# Teensylu2-0_8.net
KiCad netlist of a schematic drawn in EAGLE
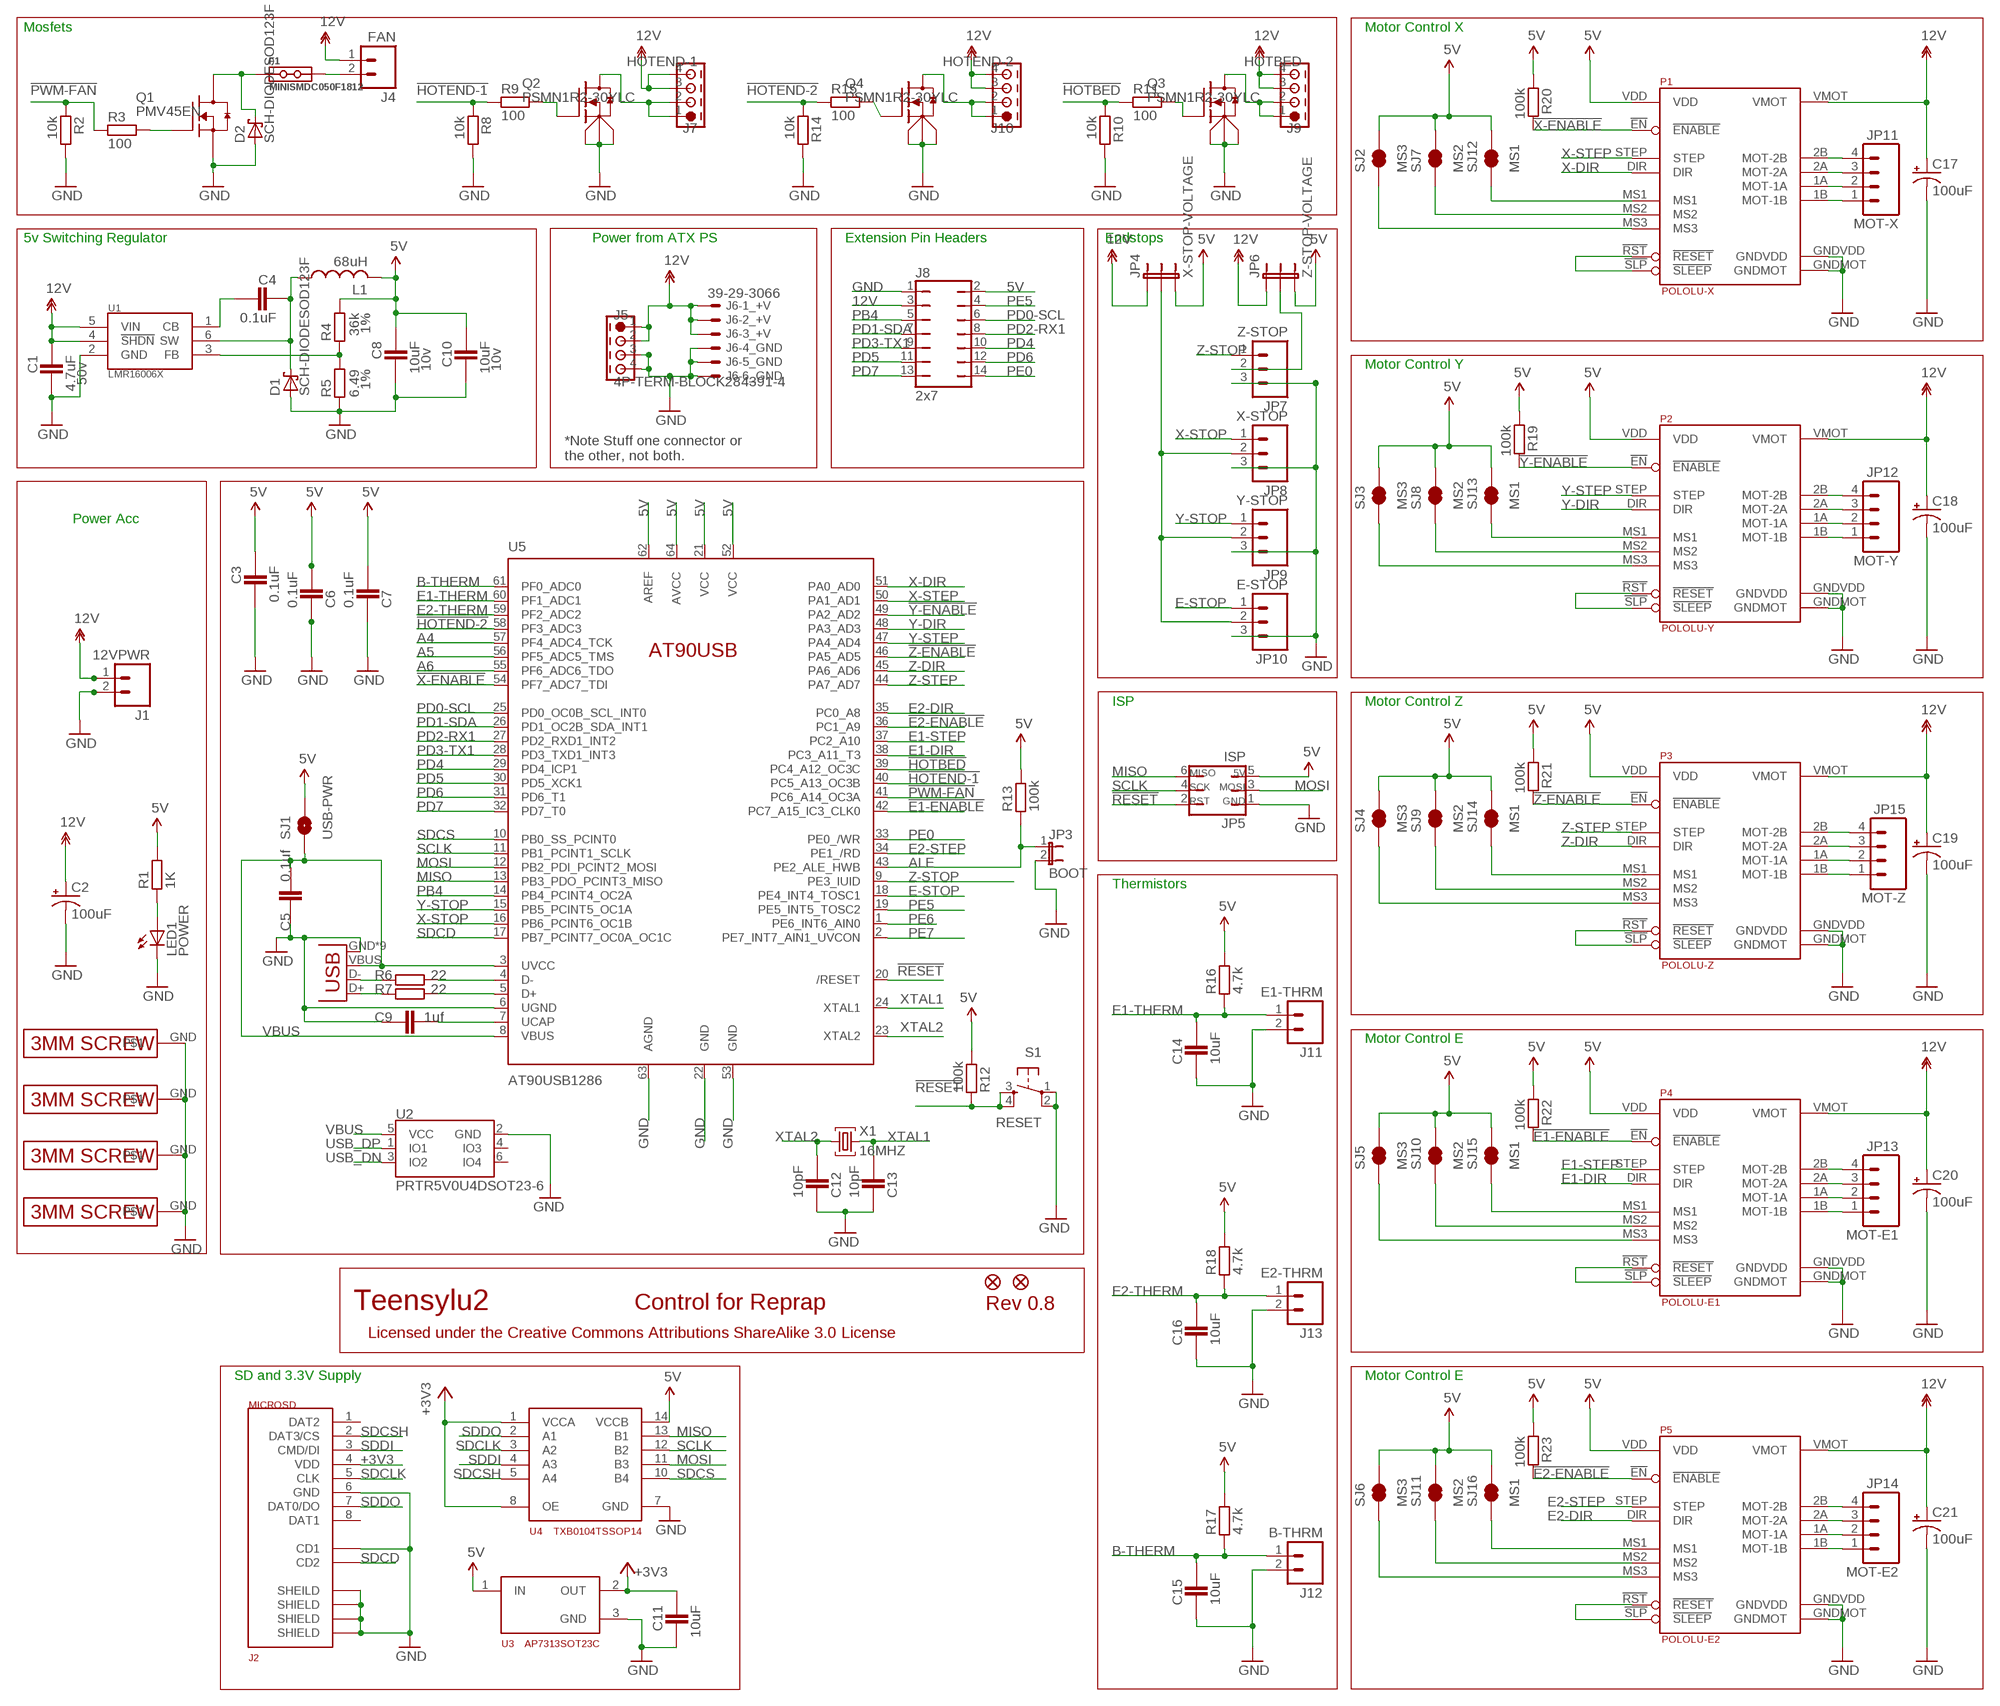
[diagram p0: schematic, sheet 1]

(export (version "E")
  (design (tool "Eeschema 10.0.6"))
  (components
    (comp (ref "C1")
      (value "4.7uF")
      (footprint "eagle-import:CAPC3215X168N")
      (fields
        (field (name "MANUFACTURER") "Yaiyo Yuden")
        (field (name "MANUFACTURER_PART_NUMBER") "UMK316AB7475KL-T")
        (field (name "VDC") "50v")
      )
      (libsource (lib "eagle-import") (part "CAPACITOR_1206"))
    )
    (comp (ref "C2")
      (value "100uF")
      (footprint "eagle-import:PANASONIC_D")
      (fields
        (field (name "MANUFACTURER") "Panasonic")
        (field (name "MANUFACTURER_PART_NUMBER") "EEE-FTH101XAP")
        (field (name "TOLERANCE") "20%")
      )
      (libsource (lib "eagle-import") (part "CPOL-USD"))
    )
    (comp (ref "C3")
      (value "0.1uF")
      (footprint "eagle-import:CAPC1608X92N")
      (fields
        (field (name "MANUFACTURER") "Murata")
        (field (name "MANUFACTURER_PART_NUMBER") "GRM188R71C104KA01D")
        (field (name "TOLERANCE") "10%")
      )
      (libsource (lib "eagle-import") (part "CAPACITOR_0603"))
    )
    (comp (ref "C4")
      (value "0.1uF")
      (footprint "eagle-import:CAPC1608X92N")
      (fields
        (field (name "MANUFACTURER") "Samsung")
        (field (name "MANUFACTURER_PART_NUMBER") "CL10B104KB8NNNC")
        (field (name "TOLERANCE") "10%")
      )
      (libsource (lib "eagle-import") (part "CAPACITOR_0603"))
    )
    (comp (ref "C5")
      (value "0.1uf")
      (footprint "eagle-import:CAPC1608X92N")
      (libsource (lib "eagle-import") (part "CAPACITOR_0603"))
    )
    (comp (ref "C6")
      (value "0.1uF")
      (footprint "eagle-import:CAPC1608X92N")
      (fields
        (field (name "MANUFACTURER") "Murata")
        (field (name "MANUFACTURER_PART_NUMBER") "GRM188R71C104KA01D")
        (field (name "TOLERANCE") "10%")
      )
      (libsource (lib "eagle-import") (part "CAPACITOR_0603"))
    )
    (comp (ref "C7")
      (value "0.1uF")
      (footprint "eagle-import:CAPC1608X92N")
      (fields
        (field (name "MANUFACTURER") "Murata")
        (field (name "MANUFACTURER_PART_NUMBER") "GRM188R71C104KA01D")
        (field (name "TOLERANCE") "10%")
      )
      (libsource (lib "eagle-import") (part "CAPACITOR_0603"))
    )
    (comp (ref "C8")
      (value "10uF")
      (footprint "eagle-import:CAPC2012X145AN")
      (fields
        (field (name "MANUFACTURER") "Murata")
        (field (name "MANUFACTURER_PART_NUMBER") "GRM21BR71A106KE51L")
        (field (name "TOLERANCE") "10%")
        (field (name "VDC") "10v")
      )
      (libsource (lib "eagle-import") (part "CAPACITOR_0805"))
    )
    (comp (ref "C9")
      (value "1uf")
      (footprint "eagle-import:CAPC1608X92N")
      (fields
        (field (name "MANUFACTURER") "Samsung")
        (field (name "MANUFACTURER_PART_NUMBER") "CL10A105MO8NNNC")
        (field (name "TOLERANCE") "20%")
      )
      (libsource (lib "eagle-import") (part "CAPACITOR_0603"))
    )
    (comp (ref "C10")
      (value "10uF")
      (footprint "eagle-import:CAPC2012X145AN")
      (fields
        (field (name "MANUFACTURER") "Murata")
        (field (name "MANUFACTURER_PART_NUMBER") "GRM21BR71A106KE51L")
        (field (name "TOLERANCE") "10%")
        (field (name "VDC") "10v")
      )
      (libsource (lib "eagle-import") (part "CAPACITOR_0805"))
    )
    (comp (ref "C11")
      (value "10uF")
      (footprint "eagle-import:CAPC1608X92N")
      (fields
        (field (name "MANUFACTURER") "Murata")
        (field (name "MANUFACTURER_PART_NUMBER") "GRM188R61C106MA73D")
        (field (name "TOLERANCE") "20%")
      )
      (libsource (lib "eagle-import") (part "CAPACITOR_0603"))
    )
    (comp (ref "C12")
      (value "10pF")
      (footprint "eagle-import:CAPC1608X92N")
      (fields
        (field (name "MANUFACTURER") "Samsung")
        (field (name "MANUFACTURER_PART_NUMBER") "CL10C100JB8NCNC")
        (field (name "TOLERANCE") "5%")
      )
      (libsource (lib "eagle-import") (part "CAPACITOR_0603"))
    )
    (comp (ref "C13")
      (value "10pF")
      (footprint "eagle-import:CAPC1608X92N")
      (fields
        (field (name "MANUFACTURER") "Samsung")
        (field (name "MANUFACTURER_PART_NUMBER") "CL10C100JB8NCNC")
        (field (name "TOLERANCE") "5%")
      )
      (libsource (lib "eagle-import") (part "CAPACITOR_0603"))
    )
    (comp (ref "C14")
      (value "10uF")
      (footprint "eagle-import:CAPC1608X92N")
      (fields
        (field (name "MANUFACTURER") "Murata")
        (field (name "MANUFACTURER_PART_NUMBER") "GRM188R61C106MA73D")
        (field (name "TOLERANCE") "20%")
      )
      (libsource (lib "eagle-import") (part "CAPACITOR_0603"))
    )
    (comp (ref "C15")
      (value "10uF")
      (footprint "eagle-import:CAPC1608X92N")
      (fields
        (field (name "MANUFACTURER") "Murata")
        (field (name "MANUFACTURER_PART_NUMBER") "GRM188R61C106MA73D")
        (field (name "TOLERANCE") "20%")
      )
      (libsource (lib "eagle-import") (part "CAPACITOR_0603"))
    )
    (comp (ref "C16")
      (value "10uF")
      (footprint "eagle-import:CAPC1608X92N")
      (fields
        (field (name "MANUFACTURER") "Murata")
        (field (name "MANUFACTURER_PART_NUMBER") "GRM188R61C106MA73D")
        (field (name "TOLERANCE") "20%")
      )
      (libsource (lib "eagle-import") (part "CAPACITOR_0603"))
    )
    (comp (ref "C17")
      (value "100uF")
      (footprint "eagle-import:PANASONIC_D")
      (fields
        (field (name "MANUFACTURER") "Panasonic")
        (field (name "MANUFACTURER_PART_NUMBER") "EEE-FTH101XAP")
        (field (name "TOLERANCE") "20%")
      )
      (libsource (lib "eagle-import") (part "CPOL-USD"))
    )
    (comp (ref "C18")
      (value "100uF")
      (footprint "eagle-import:PANASONIC_D")
      (fields
        (field (name "MANUFACTURER") "Panasonic")
        (field (name "MANUFACTURER_PART_NUMBER") "EEE-FTH101XAP")
        (field (name "TOLERANCE") "20%")
      )
      (libsource (lib "eagle-import") (part "CPOL-USD"))
    )
    (comp (ref "C19")
      (value "100uF")
      (footprint "eagle-import:PANASONIC_D")
      (fields
        (field (name "MANUFACTURER") "Panasonic")
        (field (name "MANUFACTURER_PART_NUMBER") "EEE-FTH101XAP")
        (field (name "TOLERANCE") "20%")
      )
      (libsource (lib "eagle-import") (part "CPOL-USD"))
    )
    (comp (ref "C20")
      (value "100uF")
      (footprint "eagle-import:PANASONIC_D")
      (fields
        (field (name "MANUFACTURER") "Panasonic")
        (field (name "MANUFACTURER_PART_NUMBER") "EEE-FTH101XAP")
        (field (name "TOLERANCE") "20%")
      )
      (libsource (lib "eagle-import") (part "CPOL-USD"))
    )
    (comp (ref "C21")
      (value "100uF")
      (footprint "eagle-import:PANASONIC_D")
      (fields
        (field (name "MANUFACTURER") "Panasonic")
        (field (name "MANUFACTURER_PART_NUMBER") "EEE-FTH101XAP")
        (field (name "TOLERANCE") "20%")
      )
      (libsource (lib "eagle-import") (part "CPOL-USD"))
    )
    (comp (ref "D1")
      (value "SCH-DIODESOD123F")
      (footprint "eagle-import:SOD123F")
      (fields
        (field (name "MANUFACTURER") "NXP Semiconductors")
        (field (name "MANUFACTURER_PART_NUMBER") "PMEG4010CEH,115")
        (field (name "CURRENT") "1A")
        (field (name "MANUFACTURER_1") "NXP Semiconductors")
        (field (name "MANUFACTURER_PART_NUMBER_1") "PMEG4010CEH,115")
        (field (name "REVERSE_VOLTAGE") "40V")
      )
      (libsource (lib "eagle-import") (part "SCH-DIODESOD123F"))
    )
    (comp (ref "D2")
      (value "SCH-DIODESOD123F")
      (footprint "eagle-import:SOD123F")
      (fields
        (field (name "MANUFACTURER") "NXP Semiconductors")
        (field (name "MANUFACTURER_PART_NUMBER") "PMEG4010CEH,115")
        (field (name "CURRENT") "1A")
        (field (name "MANUFACTURER_1") "NXP Semiconductors")
      )
      (libsource (lib "eagle-import") (part "SCH-DIODESOD123F"))
    )
    (comp (ref "F1")
      (value "MINISMDC050F1812")
      (footprint "eagle-import:MINISMDC")
      (fields
        (field (name "MANUFACTURER") "TE Connectivity")
        (field (name "MANUFACTURER_PART_NUMBER") "MINISMDC050F-2")
      )
      (libsource (lib "eagle-import") (part "MINISMDC050F1812"))
    )
    (comp (ref "J1")
      (value "12VPWR")
      (footprint "eagle-import:MOLEX-1X2")
      (libsource (lib "eagle-import") (part "M02POLAR"))
    )
    (comp (ref "J2")
      (value "MICROSD")
      (footprint "eagle-import:AMPHENOL-MICROSD")
      (fields
        (field (name "MANUFACTURER") "Amphenol")
        (field (name "MANUFACTURER_PART_NUMBER") "114-00841-68")
      )
      (libsource (lib "eagle-import") (part "MICROSD"))
    )
    (comp (ref "J3")
      (value "USB-MICRO-PTH")
      (footprint "eagle-import:USB-MICROB-PTH")
      (fields (field (name "MANUFACTURER") "FCI") (field (name "MANUFACTURER_PART_NUMBER") "10118194-0001LF"))
      (libsource (lib "eagle-import") (part "USB-MICRO-PTH"))
    )
    (comp (ref "J4")
      (value "FAN")
      (footprint "eagle-import:MOLEX-1X2")
      (libsource (lib "eagle-import") (part "M02POLAR"))
    )
    (comp (ref "J5")
      (value "4P-TERM-BLOCK284391-4")
      (footprint "eagle-import:284391-4")
      (fields
        (field (name "MANUFACTURER") "TE Connectivity")
        (field (name "MANUFACTURER_PART_NUMBER") "284391-4")
      )
      (libsource (lib "eagle-import") (part "4P-TERM-BLOCK284391-4"))
    )
    (comp (ref "J6")
      (value "39-29-3066")
      (footprint "eagle-import:39-29-3066")
      (fields (field (name "MANUFACTURER") "Molex") (field (name "MANUFACTURER_PART_NUMBER") "0039293066"))
      (libsource (lib "eagle-import") (part "39-29-3066"))
    )
    (comp (ref "J7")
      (value "HOTEND-1")
      (footprint "eagle-import:282834-4")
      (fields
        (field (name "MANUFACTURER") "TE Connectivity")
        (field (name "MANUFACTURER_PART_NUMBER") "282834-4")
      )
      (libsource (lib "eagle-import") (part "4P-TERM-BLOCK282834-4"))
    )
    (comp (ref "J8")
      (value "2x7")
      (footprint "eagle-import:JP7Q")
      (libsource (lib "eagle-import") (part "JP7Q"))
    )
    (comp (ref "J9")
      (value "HOTBED")
      (footprint "eagle-import:284391-4")
      (fields
        (field (name "MANUFACTURER") "TE Connectivity")
        (field (name "MANUFACTURER_PART_NUMBER") "284391-4")
      )
      (libsource (lib "eagle-import") (part "4P-TERM-BLOCK284391-4"))
    )
    (comp (ref "J10")
      (value "HOTEND-2")
      (footprint "eagle-import:282834-4")
      (fields
        (field (name "MANUFACTURER") "TE Connectivity")
        (field (name "MANUFACTURER_PART_NUMBER") "282834-4")
      )
      (libsource (lib "eagle-import") (part "4P-TERM-BLOCK282834-4"))
    )
    (comp (ref "J11")
      (value "E1-THRM")
      (footprint "eagle-import:MOLEX-1X2")
      (libsource (lib "eagle-import") (part "M02POLAR"))
    )
    (comp (ref "J12")
      (value "B-THRM")
      (footprint "eagle-import:MOLEX-1X2")
      (libsource (lib "eagle-import") (part "M02POLAR"))
    )
    (comp (ref "J13")
      (value "E2-THRM")
      (footprint "eagle-import:MOLEX-1X2")
      (libsource (lib "eagle-import") (part "M02POLAR"))
    )
    (comp (ref "JP1")
      (value "FIDUCIAL1X2.5")
      (footprint "eagle-import:FIDUCIAL-1X2.5")
      (libsource (lib "eagle-import") (part "FIDUCIAL1X2.5"))
    )
    (comp (ref "JP2")
      (value "FIDUCIAL1X2.5")
      (footprint "eagle-import:FIDUCIAL-1X2.5")
      (libsource (lib "eagle-import") (part "FIDUCIAL1X2.5"))
    )
    (comp (ref "JP3")
      (value "BOOT")
      (footprint "eagle-import:1X02")
      (libsource (lib "eagle-import") (part "JUMPER-2PTH"))
    )
    (comp (ref "JP4")
      (value "X-STOP-VOLTAGE")
      (footprint "eagle-import:1X03")
      (libsource (lib "eagle-import") (part "JUMPER-3PTH"))
    )
    (comp (ref "JP5")
      (value "ISP")
      (footprint "eagle-import:ISP")
      (libsource (lib "eagle-import") (part "PROGHEADER"))
    )
    (comp (ref "JP6")
      (value "Z-STOP-VOLTAGE")
      (footprint "eagle-import:1X03")
      (libsource (lib "eagle-import") (part "JUMPER-3PTH"))
    )
    (comp (ref "JP7")
      (value "Z-STOP")
      (footprint "eagle-import:MOLEX-1X3")
      (libsource (lib "eagle-import") (part "M03POLAR"))
    )
    (comp (ref "JP8")
      (value "X-STOP")
      (footprint "eagle-import:MOLEX-1X3")
      (libsource (lib "eagle-import") (part "M03POLAR"))
    )
    (comp (ref "JP9")
      (value "Y-STOP")
      (footprint "eagle-import:MOLEX-1X3")
      (libsource (lib "eagle-import") (part "M03POLAR"))
    )
    (comp (ref "JP10")
      (value "E-STOP")
      (footprint "eagle-import:MOLEX-1X3")
      (libsource (lib "eagle-import") (part "M03POLAR"))
    )
    (comp (ref "JP11")
      (value "MOT-X")
      (footprint "eagle-import:MOLEX-1X4")
      (libsource (lib "eagle-import") (part "M04POLAR"))
    )
    (comp (ref "JP12")
      (value "MOT-Y")
      (footprint "eagle-import:MOLEX-1X4")
      (libsource (lib "eagle-import") (part "M04POLAR"))
    )
    (comp (ref "JP13")
      (value "MOT-E1")
      (footprint "eagle-import:MOLEX-1X4")
      (libsource (lib "eagle-import") (part "M04POLAR"))
    )
    (comp (ref "JP14")
      (value "MOT-E2")
      (footprint "eagle-import:MOLEX-1X4")
      (libsource (lib "eagle-import") (part "M04POLAR"))
    )
    (comp (ref "JP15")
      (value "MOT-Z")
      (footprint "eagle-import:MOLEX-1X4")
      (libsource (lib "eagle-import") (part "M04POLAR"))
    )
    (comp (ref "L1")
      (value "68uH")
      (footprint "eagle-import:SRN6045")
      (fields
        (field (name "MANUFACTURER") "Bourns")
        (field (name "MANUFACTURER_PART_NUMBER") "SRN6045-680M")
        (field (name "MANUFACTURER_1") "Bourns")
        (field (name "MANUFACTURER_PART_NUMBER_1") "SRN6045-680M")
      )
      (libsource (lib "eagle-import") (part "INDUCTORSRN6045"))
    )
    (comp (ref "LED1")
      (value "POWER")
      (footprint "eagle-import:CHIPLED_0805")
      (fields
        (field (name "MANUFACTURER") "Kingbright")
        (field (name "MANUFACTURER_PART_NUMBER") "APT2012SGC")
      )
      (libsource (lib "eagle-import") (part "LEDCHIPLED_0805"))
    )
    (comp (ref "P1")
      (value "POLOLU-X")
      (footprint "eagle-import:POLOLU-STEPPER-PTH")
      (libsource (lib "eagle-import") (part "POLOLU-ALLEGRO"))
    )
    (comp (ref "P2")
      (value "POLOLU-Y")
      (footprint "eagle-import:POLOLU-STEPPER-PTH")
      (libsource (lib "eagle-import") (part "POLOLU-ALLEGRO"))
    )
    (comp (ref "P3")
      (value "POLOLU-Z")
      (footprint "eagle-import:POLOLU-STEPPER-PTH")
      (libsource (lib "eagle-import") (part "POLOLU-ALLEGRO"))
    )
    (comp (ref "P4")
      (value "POLOLU-E1")
      (footprint "eagle-import:POLOLU-STEPPER-PTH")
      (libsource (lib "eagle-import") (part "POLOLU-ALLEGRO"))
    )
    (comp (ref "P5")
      (value "POLOLU-E2")
      (footprint "eagle-import:POLOLU-STEPPER-PTH")
      (libsource (lib "eagle-import") (part "POLOLU-ALLEGRO"))
    )
    (comp (ref "Q1")
      (value "PMV45EN")
      (footprint "eagle-import:SOT23C")
      (fields
        (field (name "MANUFACTURER") "International Rectifier")
        (field (name "MANUFACTURER_PART_NUMBER") "IRLML2060TRPBF")
        (field (name "VOLTAGE") "60V")
      )
      (libsource (lib "eagle-import") (part "MOSFET-NCH_SOT-23"))
    )
    (comp (ref "Q2")
      (value "PSMN1R2-30YLC")
      (footprint "eagle-import:LFPACK-POWERPAK-SO8")
      (fields
        (field (name "MANUFACTURER") "NXP Semiconductors")
        (field (name "MANUFACTURER_PART_NUMBER") "PSMN1R2-30YLC,115")
        (field (name "VOLTAGE") "30V")
      )
      (libsource (lib "eagle-import") (part "PSMN1R2-30YLCPOWERPACK-S08"))
    )
    (comp (ref "Q3")
      (value "PSMN1R2-30YLC")
      (footprint "eagle-import:LFPACK-POWERPAK-SO8")
      (fields
        (field (name "MANUFACTURER") "NXP Semiconductors")
        (field (name "MANUFACTURER_PART_NUMBER") "PSMN1R2-30YLC,115")
        (field (name "VOLTAGE") "30V")
      )
      (libsource (lib "eagle-import") (part "PSMN1R2-30YLCPOWERPACK-S08"))
    )
    (comp (ref "Q4")
      (value "PSMN1R2-30YLC")
      (footprint "eagle-import:LFPACK-POWERPAK-SO8")
      (fields
        (field (name "MANUFACTURER") "NXP Semiconductors")
        (field (name "MANUFACTURER_PART_NUMBER") "PSMN1R2-30YLC,115")
        (field (name "VOLTAGE") "30V")
      )
      (libsource (lib "eagle-import") (part "PSMN1R2-30YLCPOWERPACK-S08"))
    )
    (comp (ref "R1")
      (value "1K")
      (footprint "eagle-import:RESC1608X55N")
      (libsource (lib "eagle-import") (part "RESISTOR_0603"))
    )
    (comp (ref "R2")
      (value "10k")
      (footprint "eagle-import:RESC1608X55N")
      (libsource (lib "eagle-import") (part "RESISTOR_0603"))
    )
    (comp (ref "R3")
      (value "100")
      (footprint "eagle-import:RESC1608X55N")
      (libsource (lib "eagle-import") (part "RESISTOR_0603"))
    )
    (comp (ref "R4")
      (value "36k")
      (footprint "eagle-import:RESC1608X55N")
      (fields (field (name "TOLERANCE") "1%"))
      (libsource (lib "eagle-import") (part "RESISTOR_0603"))
    )
    (comp (ref "R5")
      (value "6.49")
      (footprint "eagle-import:RESC1608X55N")
      (fields (field (name "TOLERANCE") "1%"))
      (libsource (lib "eagle-import") (part "RESISTOR_0603"))
    )
    (comp (ref "R6")
      (value "22")
      (footprint "eagle-import:RESC1608X55N")
      (libsource (lib "eagle-import") (part "RESISTOR_0603"))
    )
    (comp (ref "R7")
      (value "22")
      (footprint "eagle-import:RESC1608X55N")
      (libsource (lib "eagle-import") (part "RESISTOR_0603"))
    )
    (comp (ref "R8")
      (value "10k")
      (footprint "eagle-import:RESC1608X55N")
      (libsource (lib "eagle-import") (part "RESISTOR_0603"))
    )
    (comp (ref "R9")
      (value "100")
      (footprint "eagle-import:RESC1608X55N")
      (libsource (lib "eagle-import") (part "RESISTOR_0603"))
    )
    (comp (ref "R10")
      (value "10k")
      (footprint "eagle-import:RESC1608X55N")
      (libsource (lib "eagle-import") (part "RESISTOR_0603"))
    )
    (comp (ref "R11")
      (value "100")
      (footprint "eagle-import:RESC1608X55N")
      (libsource (lib "eagle-import") (part "RESISTOR_0603"))
    )
    (comp (ref "R12")
      (value "100k")
      (footprint "eagle-import:RESC1608X55N")
      (libsource (lib "eagle-import") (part "RESISTOR_0603"))
    )
    (comp (ref "R13")
      (value "100k")
      (footprint "eagle-import:RESC1608X55N")
      (libsource (lib "eagle-import") (part "RESISTOR_0603"))
    )
    (comp (ref "R14")
      (value "10k")
      (footprint "eagle-import:RESC1608X55N")
      (libsource (lib "eagle-import") (part "RESISTOR_0603"))
    )
    (comp (ref "R15")
      (value "100")
      (footprint "eagle-import:RESC1608X55N")
      (libsource (lib "eagle-import") (part "RESISTOR_0603"))
    )
    (comp (ref "R16")
      (value "4.7k")
      (footprint "eagle-import:RESC1608X55N")
      (libsource (lib "eagle-import") (part "RESISTOR_0603"))
    )
    (comp (ref "R17")
      (value "4.7k")
      (footprint "eagle-import:RESC1608X55N")
      (libsource (lib "eagle-import") (part "RESISTOR_0603"))
    )
    (comp (ref "R18")
      (value "4.7k")
      (footprint "eagle-import:RESC1608X55N")
      (libsource (lib "eagle-import") (part "RESISTOR_0603"))
    )
    (comp (ref "R19")
      (value "100k")
      (footprint "eagle-import:RESC1608X55N")
      (libsource (lib "eagle-import") (part "RESISTOR_0603"))
    )
    (comp (ref "R20")
      (value "100k")
      (footprint "eagle-import:RESC1608X55N")
      (libsource (lib "eagle-import") (part "RESISTOR_0603"))
    )
    (comp (ref "R21")
      (value "100k")
      (footprint "eagle-import:RESC1608X55N")
      (libsource (lib "eagle-import") (part "RESISTOR_0603"))
    )
    (comp (ref "R22")
      (value "100k")
      (footprint "eagle-import:RESC1608X55N")
      (libsource (lib "eagle-import") (part "RESISTOR_0603"))
    )
    (comp (ref "R23")
      (value "100k")
      (footprint "eagle-import:RESC1608X55N")
      (libsource (lib "eagle-import") (part "RESISTOR_0603"))
    )
    (comp (ref "S1")
      (value "RESET")
      (footprint "eagle-import:TACTILE_SWITCH_SMD")
      (libsource (lib "eagle-import") (part "TAC_SWITCHSMD"))
    )
    (comp (ref "SCREW1")
      (value "3MM-SCREW")
      (footprint "eagle-import:PLATEDSCREW")
      (libsource (lib "eagle-import") (part "3MM-SCREW"))
    )
    (comp (ref "SCREW2")
      (value "3MM-SCREW")
      (footprint "eagle-import:PLATEDSCREW")
      (libsource (lib "eagle-import") (part "3MM-SCREW"))
    )
    (comp (ref "SCREW3")
      (value "3MM-SCREW")
      (footprint "eagle-import:PLATEDSCREW")
      (libsource (lib "eagle-import") (part "3MM-SCREW"))
    )
    (comp (ref "SCREW4")
      (value "3MM-SCREW")
      (footprint "eagle-import:PLATEDSCREW")
      (libsource (lib "eagle-import") (part "3MM-SCREW"))
    )
    (comp (ref "SJ1")
      (value "USB-PWR")
      (footprint "eagle-import:SJ_2S-NO")
      (libsource (lib "eagle-import") (part "SOLDERJUMPERNO"))
    )
    (comp (ref "SJ2")
      (value "MS3")
      (footprint "eagle-import:SJ_2S-TRACE")
      (libsource (lib "eagle-import") (part "SOLDERJUMPER-NCSJ-TRACE"))
    )
    (comp (ref "SJ3")
      (value "MS3")
      (footprint "eagle-import:SJ_2S-TRACE")
      (libsource (lib "eagle-import") (part "SOLDERJUMPER-NCSJ-TRACE"))
    )
    (comp (ref "SJ4")
      (value "MS3")
      (footprint "eagle-import:SJ_2S-TRACE")
      (libsource (lib "eagle-import") (part "SOLDERJUMPER-NCSJ-TRACE"))
    )
    (comp (ref "SJ5")
      (value "MS3")
      (footprint "eagle-import:SJ_2S-TRACE")
      (libsource (lib "eagle-import") (part "SOLDERJUMPER-NCSJ-TRACE"))
    )
    (comp (ref "SJ6")
      (value "MS3")
      (footprint "eagle-import:SJ_2S-TRACE")
      (libsource (lib "eagle-import") (part "SOLDERJUMPER-NCSJ-TRACE"))
    )
    (comp (ref "SJ7")
      (value "MS2")
      (footprint "eagle-import:SJ_2S-TRACE")
      (libsource (lib "eagle-import") (part "SOLDERJUMPER-NCSJ-TRACE"))
    )
    (comp (ref "SJ8")
      (value "MS2")
      (footprint "eagle-import:SJ_2S-TRACE")
      (libsource (lib "eagle-import") (part "SOLDERJUMPER-NCSJ-TRACE"))
    )
    (comp (ref "SJ9")
      (value "MS2")
      (footprint "eagle-import:SJ_2S-TRACE")
      (libsource (lib "eagle-import") (part "SOLDERJUMPER-NCSJ-TRACE"))
    )
    (comp (ref "SJ10")
      (value "MS2")
      (footprint "eagle-import:SJ_2S-TRACE")
      (libsource (lib "eagle-import") (part "SOLDERJUMPER-NCSJ-TRACE"))
    )
    (comp (ref "SJ11")
      (value "MS2")
      (footprint "eagle-import:SJ_2S-TRACE")
      (libsource (lib "eagle-import") (part "SOLDERJUMPER-NCSJ-TRACE"))
    )
    (comp (ref "SJ12")
      (value "MS1")
      (footprint "eagle-import:SJ_2S-TRACE")
      (libsource (lib "eagle-import") (part "SOLDERJUMPER-NCSJ-TRACE"))
    )
    (comp (ref "SJ13")
      (value "MS1")
      (footprint "eagle-import:SJ_2S-TRACE")
      (libsource (lib "eagle-import") (part "SOLDERJUMPER-NCSJ-TRACE"))
    )
    (comp (ref "SJ14")
      (value "MS1")
      (footprint "eagle-import:SJ_2S-TRACE")
      (libsource (lib "eagle-import") (part "SOLDERJUMPER-NCSJ-TRACE"))
    )
    (comp (ref "SJ15")
      (value "MS1")
      (footprint "eagle-import:SJ_2S-TRACE")
      (libsource (lib "eagle-import") (part "SOLDERJUMPER-NCSJ-TRACE"))
    )
    (comp (ref "SJ16")
      (value "MS1")
      (footprint "eagle-import:SJ_2S-TRACE")
      (libsource (lib "eagle-import") (part "SOLDERJUMPER-NCSJ-TRACE"))
    )
    (comp (ref "U1")
      (value "LMR16006X")
      (footprint "eagle-import:TSOT6")
      (fields
        (field (name "MANUFACTURER") "Texas Instruments")
        (field (name "MANUFACTURER_PART_NUMBER") "LMR16006XDDCT")
      )
      (libsource (lib "eagle-import") (part "LMR16006X"))
    )
    (comp (ref "U2")
      (value "PRTR5V0U4DSOT23-6")
      (footprint "eagle-import:SOT23-6")
      (fields
        (field (name "MANUFACTURER") "NXP Semiconductors")
        (field (name "MANUFACTURER_PART_NUMBER") "PRTR5V0U4D,125")
      )
      (libsource (lib "eagle-import") (part "PRTR5V0U4DSOT23-6"))
    )
    (comp (ref "U3")
      (value "AP7313SOT23C")
      (footprint "eagle-import:SOT23C")
      (fields
        (field (name "MANUFACTURER") "Diodes Incorporated")
        (field (name "MANUFACTURER_PART_NUMBER") "AP7313-33SAG-7")
      )
      (libsource (lib "eagle-import") (part "AP7313SOT23C"))
    )
    (comp (ref "U4")
      (value "TXB0104TSSOP14")
      (footprint "eagle-import:TSSOP14")
      (fields
        (field (name "MANUFACTURER") "Texas Instruments")
        (field (name "MANUFACTURER_PART_NUMBER") "TXB0104PWR")
      )
      (libsource (lib "eagle-import") (part "TXB0104TSSOP14"))
    )
    (comp (ref "U5")
      (value "AT90USB1286")
      (footprint "eagle-import:TQFP64-2")
      (fields (field (name "MANUFACTURER") "Atmel"))
      (libsource (lib "eagle-import") (part "AT90USB"))
    )
    (comp (ref "X1")
      (value "16MHZ")
      (footprint "eagle-import:NDK-XTAL")
      (fields
        (field (name "MANUFACTURER") "NDK")
        (field (name "MANUFACTURER_PART_NUMBER") "NX5032GA-16.000000MHZ-LN-CD-1")
      )
      (libsource (lib "eagle-import") (part "XTAL"))
    )
  )
  (nets
    (net (code "1") (name "+3V3") (class "Default")
      (node (ref "C11") (pin "1") (pinfunction "1_1") (pintype "passive"))
      (node (ref "J2") (pin "4") (pinfunction "VDD_4") (pintype "power_in"))
      (node (ref "U3") (pin "2") (pinfunction "OUT_2") (pintype "power_in"))
      (node (ref "U4") (pin "1") (pinfunction "VCCA_1") (pintype "power_in"))
      (node (ref "U4") (pin "8") (pinfunction "OE_8") (pintype "input"))
    )
    (net (code "2") (name "/A4") (class "Default")
      (node (ref "U5") (pin "57") (pinfunction "PF4_ADC4_TCK_57") (pintype "bidirectional"))
    )
    (net (code "3") (name "/A5") (class "Default")
      (node (ref "U5") (pin "56") (pinfunction "PF5_ADC5_TMS_56") (pintype "bidirectional"))
    )
    (net (code "4") (name "/A6") (class "Default")
      (node (ref "U5") (pin "55") (pinfunction "PF6_ADC6_TDO_55") (pintype "bidirectional"))
    )
    (net (code "5") (name "/ALE") (class "Default")
      (node (ref "JP3") (pin "1") (pinfunction "1_1") (pintype "passive"))
      (node (ref "R13") (pin "1") (pinfunction "1_1") (pintype "passive"))
      (node (ref "U5") (pin "43") (pinfunction "PE2_ALE_HWB_43") (pintype "bidirectional"))
    )
    (net (code "6") (name "/B-THERM") (class "Default")
      (node (ref "C15") (pin "2") (pinfunction "2_2") (pintype "passive"))
      (node (ref "J12") (pin "1") (pinfunction "1_1") (pintype "passive"))
      (node (ref "R17") (pin "1") (pinfunction "1_1") (pintype "passive"))
      (node (ref "U5") (pin "61") (pinfunction "PF0_ADC0_61") (pintype "bidirectional"))
    )
    (net (code "7") (name "/E-STOP") (class "Default")
      (node (ref "JP10") (pin "1") (pinfunction "1_1") (pintype "passive"))
      (node (ref "U5") (pin "18") (pinfunction "PE4_INT4_TOSC1_18") (pintype "bidirectional"))
    )
    (net (code "8") (name "/E1-DIR") (class "Default")
      (node (ref "P4") (pin "DIR") (pinfunction "DIR_DIR") (pintype "bidirectional"))
      (node (ref "U5") (pin "38") (pinfunction "PC3_A11_T3_38") (pintype "bidirectional"))
    )
    (net (code "9") (name "/E1-STEP") (class "Default")
      (node (ref "P4") (pin "STEP") (pinfunction "STEP_STEP") (pintype "bidirectional"))
      (node (ref "U5") (pin "37") (pinfunction "PC2_A10_37") (pintype "bidirectional"))
    )
    (net (code "10") (name "/E1-THERM") (class "Default")
      (node (ref "C14") (pin "2") (pinfunction "2_2") (pintype "passive"))
      (node (ref "J11") (pin "1") (pinfunction "1_1") (pintype "passive"))
      (node (ref "R16") (pin "1") (pinfunction "1_1") (pintype "passive"))
      (node (ref "U5") (pin "60") (pinfunction "PF1_ADC1_60") (pintype "bidirectional"))
    )
    (net (code "11") (name "/E2-DIR") (class "Default")
      (node (ref "P5") (pin "DIR") (pinfunction "DIR_DIR") (pintype "bidirectional"))
      (node (ref "U5") (pin "35") (pinfunction "PC0_A8_35") (pintype "bidirectional"))
    )
    (net (code "12") (name "/E2-STEP") (class "Default")
      (node (ref "P5") (pin "STEP") (pinfunction "STEP_STEP") (pintype "bidirectional"))
      (node (ref "U5") (pin "34") (pinfunction "PE1_/RD_34") (pintype "bidirectional"))
    )
    (net (code "13") (name "/E2-THERM") (class "Default")
      (node (ref "C16") (pin "2") (pinfunction "2_2") (pintype "passive"))
      (node (ref "J13") (pin "1") (pinfunction "1_1") (pintype "passive"))
      (node (ref "R18") (pin "1") (pinfunction "1_1") (pintype "passive"))
      (node (ref "U5") (pin "59") (pinfunction "PF2_ADC2_59") (pintype "bidirectional"))
    )
    (net (code "14") (name "/MISO") (class "Default")
      (node (ref "JP5") (pin "6") (pinfunction "6_6") (pintype "passive"))
      (node (ref "U4") (pin "13") (pinfunction "B1_13") (pintype "bidirectional"))
      (node (ref "U5") (pin "13") (pinfunction "PB3_PDO_PCINT3_MISO_13") (pintype "bidirectional"))
    )
    (net (code "15") (name "/MOSI") (class "Default")
      (node (ref "JP5") (pin "3") (pinfunction "3_3") (pintype "passive"))
      (node (ref "U4") (pin "11") (pinfunction "B3_11") (pintype "bidirectional"))
      (node (ref "U5") (pin "12") (pinfunction "PB2_PDI_PCINT2_MOSI_12") (pintype "bidirectional"))
    )
    (net (code "16") (name "/PB4") (class "Default")
      (node (ref "J8") (pin "5") (pinfunction "5_5") (pintype "passive"))
      (node (ref "U5") (pin "14") (pinfunction "PB4_PCINT4_OC2A_14") (pintype "bidirectional"))
    )
    (net (code "17") (name "/PD0-SCL") (class "Default")
      (node (ref "J8") (pin "6") (pinfunction "6_6") (pintype "passive"))
      (node (ref "U5") (pin "25") (pinfunction "PD0_OC0B_SCL_INT0_25") (pintype "bidirectional"))
    )
    (net (code "18") (name "/PD1-SDA") (class "Default")
      (node (ref "J8") (pin "7") (pinfunction "7_7") (pintype "passive"))
      (node (ref "U5") (pin "26") (pinfunction "PD1_OC2B_SDA_INT1_26") (pintype "bidirectional"))
    )
    (net (code "19") (name "/PD2-RX1") (class "Default")
      (node (ref "J8") (pin "8") (pinfunction "8_8") (pintype "passive"))
      (node (ref "U5") (pin "27") (pinfunction "PD2_RXD1_INT2_27") (pintype "bidirectional"))
    )
    (net (code "20") (name "/PD3-TX1") (class "Default")
      (node (ref "J8") (pin "9") (pinfunction "9_9") (pintype "passive"))
      (node (ref "U5") (pin "28") (pinfunction "PD3_TXD1_INT3_28") (pintype "bidirectional"))
    )
    (net (code "21") (name "/PD4") (class "Default")
      (node (ref "J8") (pin "10") (pinfunction "10_10") (pintype "passive"))
      (node (ref "U5") (pin "29") (pinfunction "PD4_ICP1_29") (pintype "bidirectional"))
    )
    (net (code "22") (name "/PD5") (class "Default")
      (node (ref "J8") (pin "11") (pinfunction "11_11") (pintype "passive"))
      (node (ref "U5") (pin "30") (pinfunction "PD5_XCK1_30") (pintype "bidirectional"))
    )
    (net (code "23") (name "/PD6") (class "Default")
      (node (ref "J8") (pin "12") (pinfunction "12_12") (pintype "passive"))
      (node (ref "U5") (pin "31") (pinfunction "PD6_T1_31") (pintype "bidirectional"))
    )
    (net (code "24") (name "/PD7") (class "Default")
      (node (ref "J8") (pin "13") (pinfunction "13_13") (pintype "passive"))
      (node (ref "U5") (pin "32") (pinfunction "PD7_T0_32") (pintype "bidirectional"))
    )
    (net (code "25") (name "/PE0") (class "Default")
      (node (ref "J8") (pin "14") (pinfunction "14_14") (pintype "passive"))
      (node (ref "U5") (pin "33") (pinfunction "PE0_/WR_33") (pintype "bidirectional"))
    )
    (net (code "26") (name "/PE5") (class "Default")
      (node (ref "J8") (pin "4") (pinfunction "4_4") (pintype "passive"))
      (node (ref "U5") (pin "19") (pinfunction "PE5_INT5_TOSC2_19") (pintype "bidirectional"))
    )
    (net (code "27") (name "/PE6") (class "Default")
      (node (ref "U5") (pin "1") (pinfunction "PE6_INT6_AIN0_1") (pintype "bidirectional"))
    )
    (net (code "28") (name "/PE7") (class "Default")
      (node (ref "U5") (pin "2") (pinfunction "PE7_INT7_AIN1_UVCON_2") (pintype "bidirectional"))
    )
    (net (code "29") (name "/SCLK") (class "Default")
      (node (ref "JP5") (pin "4") (pinfunction "4_4") (pintype "passive"))
      (node (ref "U4") (pin "12") (pinfunction "B2_12") (pintype "bidirectional"))
      (node (ref "U5") (pin "11") (pinfunction "PB1_PCINT1_SCLK_11") (pintype "bidirectional"))
    )
    (net (code "30") (name "/SDCD") (class "Default")
      (node (ref "J2") (pin "CD2") (pinfunction "CD2_CD2") (pintype "bidirectional"))
      (node (ref "U5") (pin "17") (pinfunction "PB7_PCINT7_OC0A_OC1C_17") (pintype "bidirectional"))
    )
    (net (code "31") (name "/SDCLK") (class "Default")
      (node (ref "J2") (pin "5") (pinfunction "CLK_5") (pintype "input"))
      (node (ref "U4") (pin "3") (pinfunction "A2_3") (pintype "bidirectional"))
    )
    (net (code "32") (name "/SDCS") (class "Default")
      (node (ref "U4") (pin "10") (pinfunction "B4_10") (pintype "bidirectional"))
      (node (ref "U5") (pin "10") (pinfunction "PB0_SS_PCINT0_10") (pintype "bidirectional"))
    )
    (net (code "33") (name "/SDCSH") (class "Default")
      (node (ref "J2") (pin "2") (pinfunction "DAT3/CS_2") (pintype "bidirectional"))
      (node (ref "U4") (pin "5") (pinfunction "A4_5") (pintype "bidirectional"))
    )
    (net (code "34") (name "/SDDI") (class "Default")
      (node (ref "J2") (pin "3") (pinfunction "CMD/DI_3") (pintype "input"))
      (node (ref "U4") (pin "4") (pinfunction "A3_4") (pintype "bidirectional"))
    )
    (net (code "35") (name "/SDDO") (class "Default")
      (node (ref "J2") (pin "7") (pinfunction "DAT0/DO_7") (pintype "bidirectional"))
      (node (ref "U4") (pin "2") (pinfunction "A1_2") (pintype "bidirectional"))
    )
    (net (code "36") (name "/USB_DN") (class "Default")
      (node (ref "J3") (pin "D-") (pinfunction "D-_D-") (pintype "bidirectional"))
      (node (ref "R6") (pin "1") (pinfunction "1_1") (pintype "passive"))
      (node (ref "U2") (pin "3") (pinfunction "IO2_3") (pintype "bidirectional"))
    )
    (net (code "37") (name "/USB_DP") (class "Default")
      (node (ref "J3") (pin "D+") (pinfunction "D+_D+") (pintype "bidirectional"))
      (node (ref "R7") (pin "1") (pinfunction "1_1") (pintype "passive"))
      (node (ref "U2") (pin "1") (pinfunction "IO1_1") (pintype "bidirectional"))
    )
    (net (code "38") (name "/VBUS") (class "Default")
      (node (ref "C5") (pin "2") (pinfunction "2_2") (pintype "passive"))
      (node (ref "J3") (pin "VBUS") (pinfunction "VBUS_VBUS") (pintype "bidirectional"))
      (node (ref "SJ1") (pin "1") (pinfunction "1_1") (pintype "passive"))
      (node (ref "U2") (pin "5") (pinfunction "VCC_5") (pintype "power_in"))
      (node (ref "U5") (pin "3") (pinfunction "UVCC_3") (pintype "power_in"))
      (node (ref "U5") (pin "8") (pinfunction "VBUS_8") (pintype "bidirectional"))
    )
    (net (code "39") (name "/X-DIR") (class "Default")
      (node (ref "P1") (pin "DIR") (pinfunction "DIR_DIR") (pintype "bidirectional"))
      (node (ref "U5") (pin "51") (pinfunction "PA0_AD0_51") (pintype "bidirectional"))
    )
    (net (code "40") (name "/X-STEP") (class "Default")
      (node (ref "P1") (pin "STEP") (pinfunction "STEP_STEP") (pintype "bidirectional"))
      (node (ref "U5") (pin "50") (pinfunction "PA1_AD1_50") (pintype "bidirectional"))
    )
    (net (code "41") (name "/X-STOP") (class "Default")
      (node (ref "JP8") (pin "1") (pinfunction "1_1") (pintype "passive"))
      (node (ref "U5") (pin "16") (pinfunction "PB6_PCINT6_OC1B_16") (pintype "bidirectional"))
    )
    (net (code "42") (name "/XTAL1") (class "Default")
      (node (ref "C13") (pin "2") (pinfunction "2_2") (pintype "passive"))
      (node (ref "U5") (pin "24") (pinfunction "XTAL1_24") (pintype "passive"))
      (node (ref "X1") (pin "P$2") (pinfunction "2_P$2") (pintype "passive"))
    )
    (net (code "43") (name "/XTAL2") (class "Default")
      (node (ref "C12") (pin "2") (pinfunction "2_2") (pintype "passive"))
      (node (ref "U5") (pin "23") (pinfunction "XTAL2_23") (pintype "passive"))
      (node (ref "X1") (pin "P$1") (pinfunction "1_P$1") (pintype "passive"))
    )
    (net (code "44") (name "/Y-DIR") (class "Default")
      (node (ref "P2") (pin "DIR") (pinfunction "DIR_DIR") (pintype "bidirectional"))
      (node (ref "U5") (pin "48") (pinfunction "PA3_AD3_48") (pintype "bidirectional"))
    )
    (net (code "45") (name "/Y-STEP") (class "Default")
      (node (ref "P2") (pin "STEP") (pinfunction "STEP_STEP") (pintype "bidirectional"))
      (node (ref "U5") (pin "47") (pinfunction "PA4_AD4_47") (pintype "bidirectional"))
    )
    (net (code "46") (name "/Y-STOP") (class "Default")
      (node (ref "JP9") (pin "1") (pinfunction "1_1") (pintype "passive"))
      (node (ref "U5") (pin "15") (pinfunction "PB5_PCINT5_OC1A_15") (pintype "bidirectional"))
    )
    (net (code "47") (name "/Z-DIR") (class "Default")
      (node (ref "P3") (pin "DIR") (pinfunction "DIR_DIR") (pintype "bidirectional"))
      (node (ref "U5") (pin "45") (pinfunction "PA6_AD6_45") (pintype "bidirectional"))
    )
    (net (code "48") (name "/Z-STEP") (class "Default")
      (node (ref "P3") (pin "STEP") (pinfunction "STEP_STEP") (pintype "bidirectional"))
      (node (ref "U5") (pin "44") (pinfunction "PA7_AD7_44") (pintype "bidirectional"))
    )
    (net (code "49") (name "/Z-STOP") (class "Default")
      (node (ref "JP7") (pin "1") (pinfunction "1_1") (pintype "passive"))
      (node (ref "U5") (pin "9") (pinfunction "PE3_IUID_9") (pintype "bidirectional"))
    )
    (net (code "50") (name "/~{E1-ENABLE}") (class "Default")
      (node (ref "P4") (pin "!EN") (pinfunction "~{ENABLE}_!EN") (pintype "input"))
      (node (ref "R22") (pin "2") (pinfunction "2_2") (pintype "passive"))
      (node (ref "U5") (pin "42") (pinfunction "PC7_A15_IC3_CLK0_42") (pintype "bidirectional"))
    )
    (net (code "51") (name "/~{E2-ENABLE}") (class "Default")
      (node (ref "P5") (pin "!EN") (pinfunction "~{ENABLE}_!EN") (pintype "input"))
      (node (ref "R23") (pin "2") (pinfunction "2_2") (pintype "passive"))
      (node (ref "U5") (pin "36") (pinfunction "PC1_A9_36") (pintype "bidirectional"))
    )
    (net (code "52") (name "/~{HOTBED}") (class "Default")
      (node (ref "R10") (pin "1") (pinfunction "1_1") (pintype "passive"))
      (node (ref "R11") (pin "1") (pinfunction "1_1") (pintype "passive"))
      (node (ref "U5") (pin "39") (pinfunction "PC4_A12_OC3C_39") (pintype "bidirectional"))
    )
    (net (code "53") (name "/~{HOTEND-1}") (class "Default")
      (node (ref "R8") (pin "1") (pinfunction "1_1") (pintype "passive"))
      (node (ref "R9") (pin "1") (pinfunction "1_1") (pintype "passive"))
      (node (ref "U5") (pin "40") (pinfunction "PC5_A13_OC3B_40") (pintype "bidirectional"))
    )
    (net (code "54") (name "/~{HOTEND-2}") (class "Default")
      (node (ref "R14") (pin "1") (pinfunction "1_1") (pintype "passive"))
      (node (ref "R15") (pin "1") (pinfunction "1_1") (pintype "passive"))
      (node (ref "U5") (pin "58") (pinfunction "PF3_ADC3_58") (pintype "bidirectional"))
    )
    (net (code "55") (name "/~{PWM-FAN}") (class "Default")
      (node (ref "R2") (pin "1") (pinfunction "1_1") (pintype "passive"))
      (node (ref "R3") (pin "1") (pinfunction "1_1") (pintype "passive"))
      (node (ref "U5") (pin "41") (pinfunction "PC6_A14_OC3A_41") (pintype "bidirectional"))
    )
    (net (code "56") (name "/~{RESET}") (class "Default")
      (node (ref "JP5") (pin "2") (pinfunction "2_2") (pintype "passive"))
      (node (ref "R12") (pin "1") (pinfunction "1_1") (pintype "passive"))
      (node (ref "S1") (pin "3") (pinfunction "3_3") (pintype "passive"))
      (node (ref "S1") (pin "4") (pinfunction "4_4") (pintype "passive"))
      (node (ref "U5") (pin "20") (pinfunction "/RESET_20") (pintype "bidirectional"))
    )
    (net (code "57") (name "/~{X-ENABLE}") (class "Default")
      (node (ref "P1") (pin "!EN") (pinfunction "~{ENABLE}_!EN") (pintype "input"))
      (node (ref "R20") (pin "2") (pinfunction "2_2") (pintype "passive"))
      (node (ref "U5") (pin "54") (pinfunction "PF7_ADC7_TDI_54") (pintype "bidirectional"))
    )
    (net (code "58") (name "/~{Y-ENABLE}") (class "Default")
      (node (ref "P2") (pin "!EN") (pinfunction "~{ENABLE}_!EN") (pintype "input"))
      (node (ref "R19") (pin "2") (pinfunction "2_2") (pintype "passive"))
      (node (ref "U5") (pin "49") (pinfunction "PA2_AD2_49") (pintype "bidirectional"))
    )
    (net (code "59") (name "/~{Z-ENABLE}") (class "Default")
      (node (ref "P3") (pin "!EN") (pinfunction "~{ENABLE}_!EN") (pintype "input"))
      (node (ref "R21") (pin "2") (pinfunction "2_2") (pintype "passive"))
      (node (ref "U5") (pin "46") (pinfunction "PA5_AD5_46") (pintype "bidirectional"))
    )
    (net (code "60") (name "5V") (class "Default")
      (node (ref "C10") (pin "1") (pinfunction "1_1") (pintype "passive"))
      (node (ref "C3") (pin "1") (pinfunction "1_1") (pintype "passive"))
      (node (ref "C6") (pin "2") (pinfunction "2_2") (pintype "passive"))
      (node (ref "C7") (pin "2") (pinfunction "2_2") (pintype "passive"))
      (node (ref "C8") (pin "1") (pinfunction "1_1") (pintype "passive"))
      (node (ref "J8") (pin "2") (pinfunction "2_2") (pintype "passive"))
      (node (ref "JP4") (pin "3") (pinfunction "3_3") (pintype "passive"))
      (node (ref "JP5") (pin "5") (pinfunction "5_5") (pintype "passive"))
      (node (ref "JP6") (pin "3") (pinfunction "3_3") (pintype "passive"))
      (node (ref "L1") (pin "2") (pinfunction "2_2") (pintype "passive"))
      (node (ref "P1") (pin "VDD") (pinfunction "VDD_VDD") (pintype "power_in"))
      (node (ref "P2") (pin "VDD") (pinfunction "VDD_VDD") (pintype "power_in"))
      (node (ref "P3") (pin "VDD") (pinfunction "VDD_VDD") (pintype "power_in"))
      (node (ref "P4") (pin "VDD") (pinfunction "VDD_VDD") (pintype "power_in"))
      (node (ref "P5") (pin "VDD") (pinfunction "VDD_VDD") (pintype "power_in"))
      (node (ref "R1") (pin "2") (pinfunction "2_2") (pintype "passive"))
      (node (ref "R12") (pin "2") (pinfunction "2_2") (pintype "passive"))
      (node (ref "R13") (pin "2") (pinfunction "2_2") (pintype "passive"))
      (node (ref "R16") (pin "2") (pinfunction "2_2") (pintype "passive"))
      (node (ref "R17") (pin "2") (pinfunction "2_2") (pintype "passive"))
      (node (ref "R18") (pin "2") (pinfunction "2_2") (pintype "passive"))
      (node (ref "R19") (pin "1") (pinfunction "1_1") (pintype "passive"))
      (node (ref "R20") (pin "1") (pinfunction "1_1") (pintype "passive"))
      (node (ref "R21") (pin "1") (pinfunction "1_1") (pintype "passive"))
      (node (ref "R22") (pin "1") (pinfunction "1_1") (pintype "passive"))
      (node (ref "R23") (pin "1") (pinfunction "1_1") (pintype "passive"))
      (node (ref "R4") (pin "1") (pinfunction "1_1") (pintype "passive"))
      (node (ref "SJ1") (pin "2") (pinfunction "2_2") (pintype "passive"))
      (node (ref "SJ10") (pin "2") (pinfunction "2_2") (pintype "passive"))
      (node (ref "SJ11") (pin "2") (pinfunction "2_2") (pintype "passive"))
      (node (ref "SJ12") (pin "2") (pinfunction "2_2") (pintype "passive"))
      (node (ref "SJ13") (pin "2") (pinfunction "2_2") (pintype "passive"))
      (node (ref "SJ14") (pin "2") (pinfunction "2_2") (pintype "passive"))
      (node (ref "SJ15") (pin "2") (pinfunction "2_2") (pintype "passive"))
      (node (ref "SJ16") (pin "2") (pinfunction "2_2") (pintype "passive"))
      (node (ref "SJ2") (pin "2") (pinfunction "2_2") (pintype "passive"))
      (node (ref "SJ3") (pin "2") (pinfunction "2_2") (pintype "passive"))
      (node (ref "SJ4") (pin "2") (pinfunction "2_2") (pintype "passive"))
      (node (ref "SJ5") (pin "2") (pinfunction "2_2") (pintype "passive"))
      (node (ref "SJ6") (pin "2") (pinfunction "2_2") (pintype "passive"))
      (node (ref "SJ7") (pin "2") (pinfunction "2_2") (pintype "passive"))
      (node (ref "SJ8") (pin "2") (pinfunction "2_2") (pintype "passive"))
      (node (ref "SJ9") (pin "2") (pinfunction "2_2") (pintype "passive"))
      (node (ref "U3") (pin "1") (pinfunction "IN_1") (pintype "power_in"))
      (node (ref "U4") (pin "14") (pinfunction "VCCB_14") (pintype "power_in"))
      (node (ref "U5") (pin "21") (pinfunction "VCC_21") (pintype "power_in"))
      (node (ref "U5") (pin "52") (pinfunction "VCC_52") (pintype "power_in"))
      (node (ref "U5") (pin "62") (pinfunction "AREF_62") (pintype "power_in"))
      (node (ref "U5") (pin "64") (pinfunction "AVCC_64") (pintype "power_in"))
    )
    (net (code "61") (name "12V") (class "Default")
      (node (ref "C1") (pin "1") (pinfunction "1_1") (pintype "passive"))
      (node (ref "C17") (pin "+") (pinfunction "+_+") (pintype "passive"))
      (node (ref "C18") (pin "+") (pinfunction "+_+") (pintype "passive"))
      (node (ref "C19") (pin "+") (pinfunction "+_+") (pintype "passive"))
      (node (ref "C2") (pin "+") (pinfunction "+_+") (pintype "passive"))
      (node (ref "C20") (pin "+") (pinfunction "+_+") (pintype "passive"))
      (node (ref "C21") (pin "+") (pinfunction "+_+") (pintype "passive"))
      (node (ref "J1") (pin "1") (pinfunction "1_1") (pintype "passive"))
      (node (ref "J10") (pin "3") (pinfunction "3_3") (pintype "power_in"))
      (node (ref "J10") (pin "4") (pinfunction "4_4") (pintype "power_in"))
      (node (ref "J4") (pin "1") (pinfunction "1_1") (pintype "passive"))
      (node (ref "J5") (pin "1") (pinfunction "1_1") (pintype "power_in"))
      (node (ref "J5") (pin "2") (pinfunction "2_2") (pintype "power_in"))
      (node (ref "J6") (pin "1") (pinfunction "S_1") (pintype "passive"))
      (node (ref "J6") (pin "2") (pinfunction "S_2") (pintype "passive"))
      (node (ref "J6") (pin "3") (pinfunction "S_3") (pintype "passive"))
      (node (ref "J7") (pin "3") (pinfunction "3_3") (pintype "power_in"))
      (node (ref "J7") (pin "4") (pinfunction "4_4") (pintype "power_in"))
      (node (ref "J8") (pin "3") (pinfunction "3_3") (pintype "passive"))
      (node (ref "J9") (pin "3") (pinfunction "3_3") (pintype "power_in"))
      (node (ref "J9") (pin "4") (pinfunction "4_4") (pintype "power_in"))
      (node (ref "JP4") (pin "1") (pinfunction "1_1") (pintype "passive"))
      (node (ref "JP6") (pin "1") (pinfunction "1_1") (pintype "passive"))
      (node (ref "P1") (pin "VMOT") (pinfunction "VMOT_VMOT") (pintype "power_in"))
      (node (ref "P2") (pin "VMOT") (pinfunction "VMOT_VMOT") (pintype "power_in"))
      (node (ref "P3") (pin "VMOT") (pinfunction "VMOT_VMOT") (pintype "power_in"))
      (node (ref "P4") (pin "VMOT") (pinfunction "VMOT_VMOT") (pintype "power_in"))
      (node (ref "P5") (pin "VMOT") (pinfunction "VMOT_VMOT") (pintype "power_in"))
      (node (ref "U1") (pin "4") (pinfunction "~{SHDN}_4") (pintype "input"))
      (node (ref "U1") (pin "5") (pinfunction "VIN_5") (pintype "power_in"))
    )
    (net (code "62") (name "GND") (class "Default")
      (node (ref "C1") (pin "2") (pinfunction "2_2") (pintype "passive"))
      (node (ref "C10") (pin "2") (pinfunction "2_2") (pintype "passive"))
      (node (ref "C11") (pin "2") (pinfunction "2_2") (pintype "passive"))
      (node (ref "C12") (pin "1") (pinfunction "1_1") (pintype "passive"))
      (node (ref "C13") (pin "1") (pinfunction "1_1") (pintype "passive"))
      (node (ref "C14") (pin "1") (pinfunction "1_1") (pintype "passive"))
      (node (ref "C15") (pin "1") (pinfunction "1_1") (pintype "passive"))
      (node (ref "C16") (pin "1") (pinfunction "1_1") (pintype "passive"))
      (node (ref "C17") (pin "-") (pinfunction "-_-") (pintype "passive"))
      (node (ref "C18") (pin "-") (pinfunction "-_-") (pintype "passive"))
      (node (ref "C19") (pin "-") (pinfunction "-_-") (pintype "passive"))
      (node (ref "C2") (pin "-") (pinfunction "-_-") (pintype "passive"))
      (node (ref "C20") (pin "-") (pinfunction "-_-") (pintype "passive"))
      (node (ref "C21") (pin "-") (pinfunction "-_-") (pintype "passive"))
      (node (ref "C3") (pin "2") (pinfunction "2_2") (pintype "passive"))
      (node (ref "C5") (pin "1") (pinfunction "1_1") (pintype "passive"))
      (node (ref "C6") (pin "1") (pinfunction "1_1") (pintype "passive"))
      (node (ref "C7") (pin "1") (pinfunction "1_1") (pintype "passive"))
      (node (ref "C8") (pin "2") (pinfunction "2_2") (pintype "passive"))
      (node (ref "C9") (pin "1") (pinfunction "1_1") (pintype "passive"))
      (node (ref "D1") (pin "A") (pinfunction "A_A") (pintype "passive"))
      (node (ref "D2") (pin "A") (pinfunction "A_A") (pintype "passive"))
      (node (ref "J1") (pin "2") (pinfunction "2_2") (pintype "passive"))
      (node (ref "J11") (pin "2") (pinfunction "2_2") (pintype "passive"))
      (node (ref "J12") (pin "2") (pinfunction "2_2") (pintype "passive"))
      (node (ref "J13") (pin "2") (pinfunction "2_2") (pintype "passive"))
      (node (ref "J2") (pin "6") (pinfunction "GND_6") (pintype "power_in"))
      (node (ref "J2") (pin "C1") (pinfunction "SHEILD_C1") (pintype "bidirectional"))
      (node (ref "J2") (pin "C2") (pinfunction "SHIELD_C2") (pintype "bidirectional"))
      (node (ref "J2") (pin "C3") (pinfunction "SHIELD_C3") (pintype "bidirectional"))
      (node (ref "J2") (pin "C4") (pinfunction "SHIELD_C4") (pintype "bidirectional"))
      (node (ref "J2") (pin "CD1") (pinfunction "CD1_CD1") (pintype "bidirectional"))
      (node (ref "J3") (pin "GND") (pinfunction "GND_GND") (pintype "bidirectional"))
      (node (ref "J3") (pin "GND1") (pinfunction "GND_GND1") (pintype "bidirectional"))
      (node (ref "J3") (pin "GND2") (pinfunction "GND_GND2") (pintype "bidirectional"))
      (node (ref "J3") (pin "GND3") (pinfunction "GND_GND3") (pintype "bidirectional"))
      (node (ref "J3") (pin "GND4") (pinfunction "GND_GND4") (pintype "bidirectional"))
      (node (ref "J3") (pin "GND5") (pinfunction "GND_GND5") (pintype "bidirectional"))
      (node (ref "J3") (pin "GND6") (pinfunction "GND_GND6") (pintype "bidirectional"))
      (node (ref "J3") (pin "GND7") (pinfunction "GND_GND7") (pintype "bidirectional"))
      (node (ref "J3") (pin "GND8") (pinfunction "GND_GND8") (pintype "bidirectional"))
      (node (ref "J5") (pin "3") (pinfunction "3_3") (pintype "power_in"))
      (node (ref "J5") (pin "4") (pinfunction "4_4") (pintype "power_in"))
      (node (ref "J6") (pin "4") (pinfunction "S_4") (pintype "passive"))
      (node (ref "J6") (pin "5") (pinfunction "S_5") (pintype "passive"))
      (node (ref "J6") (pin "6") (pinfunction "S_6") (pintype "passive"))
      (node (ref "J8") (pin "1") (pinfunction "1_1") (pintype "passive"))
      (node (ref "JP10") (pin "3") (pinfunction "3_3") (pintype "passive"))
      (node (ref "JP3") (pin "2") (pinfunction "2_2") (pintype "passive"))
      (node (ref "JP5") (pin "1") (pinfunction "1_1") (pintype "passive"))
      (node (ref "JP7") (pin "3") (pinfunction "3_3") (pintype "passive"))
      (node (ref "JP8") (pin "3") (pinfunction "3_3") (pintype "passive"))
      (node (ref "JP9") (pin "3") (pinfunction "3_3") (pintype "passive"))
      (node (ref "LED1") (pin "C") (pinfunction "C_C") (pintype "passive"))
      (node (ref "P1") (pin "GNDMOT") (pinfunction "GNDMOT_GNDMOT") (pintype "power_in"))
      (node (ref "P1") (pin "GNDVDD") (pinfunction "GNDVDD_GNDVDD") (pintype "power_in"))
      (node (ref "P2") (pin "GNDMOT") (pinfunction "GNDMOT_GNDMOT") (pintype "power_in"))
      (node (ref "P2") (pin "GNDVDD") (pinfunction "GNDVDD_GNDVDD") (pintype "power_in"))
      (node (ref "P3") (pin "GNDMOT") (pinfunction "GNDMOT_GNDMOT") (pintype "power_in"))
      (node (ref "P3") (pin "GNDVDD") (pinfunction "GNDVDD_GNDVDD") (pintype "power_in"))
      (node (ref "P4") (pin "GNDMOT") (pinfunction "GNDMOT_GNDMOT") (pintype "power_in"))
      (node (ref "P4") (pin "GNDVDD") (pinfunction "GNDVDD_GNDVDD") (pintype "power_in"))
      (node (ref "P5") (pin "GNDMOT") (pinfunction "GNDMOT_GNDMOT") (pintype "power_in"))
      (node (ref "P5") (pin "GNDVDD") (pinfunction "GNDVDD_GNDVDD") (pintype "power_in"))
      (node (ref "Q1") (pin "2") (pinfunction "S_2") (pintype "passive"))
      (node (ref "Q2") (pin "1") (pinfunction "S1_1") (pintype "passive"))
      (node (ref "Q2") (pin "2") (pinfunction "S2_2") (pintype "passive"))
      (node (ref "Q2") (pin "3") (pinfunction "S3_3") (pintype "passive"))
      (node (ref "Q3") (pin "1") (pinfunction "S1_1") (pintype "passive"))
      (node (ref "Q3") (pin "2") (pinfunction "S2_2") (pintype "passive"))
      (node (ref "Q3") (pin "3") (pinfunction "S3_3") (pintype "passive"))
      (node (ref "Q4") (pin "1") (pinfunction "S1_1") (pintype "passive"))
      (node (ref "Q4") (pin "2") (pinfunction "S2_2") (pintype "passive"))
      (node (ref "Q4") (pin "3") (pinfunction "S3_3") (pintype "passive"))
      (node (ref "R10") (pin "2") (pinfunction "2_2") (pintype "passive"))
      (node (ref "R14") (pin "2") (pinfunction "2_2") (pintype "passive"))
      (node (ref "R2") (pin "2") (pinfunction "2_2") (pintype "passive"))
      (node (ref "R5") (pin "2") (pinfunction "2_2") (pintype "passive"))
      (node (ref "R8") (pin "2") (pinfunction "2_2") (pintype "passive"))
      (node (ref "S1") (pin "1") (pinfunction "1_1") (pintype "passive"))
      (node (ref "S1") (pin "2") (pinfunction "2_2") (pintype "passive"))
      (node (ref "SCREW1") (pin "GND") (pinfunction "P$1_GND") (pintype "bidirectional"))
      (node (ref "SCREW2") (pin "GND") (pinfunction "P$1_GND") (pintype "bidirectional"))
      (node (ref "SCREW3") (pin "GND") (pinfunction "P$1_GND") (pintype "bidirectional"))
      (node (ref "SCREW4") (pin "GND") (pinfunction "P$1_GND") (pintype "bidirectional"))
      (node (ref "U1") (pin "2") (pinfunction "GND_2") (pintype "power_in"))
      (node (ref "U2") (pin "2") (pinfunction "GND_2") (pintype "power_in"))
      (node (ref "U3") (pin "3") (pinfunction "GND_3") (pintype "power_in"))
      (node (ref "U4") (pin "7") (pinfunction "GND_7") (pintype "power_in"))
      (node (ref "U5") (pin "22") (pinfunction "GND_22") (pintype "power_in"))
      (node (ref "U5") (pin "53") (pinfunction "GND_53") (pintype "power_in"))
      (node (ref "U5") (pin "6") (pinfunction "UGND_6") (pintype "power_in"))
      (node (ref "U5") (pin "63") (pinfunction "AGND_63") (pintype "power_in"))
    )
    (net (code "63") (name "Net-(F1-PadP$2)") (class "Default")
      (node (ref "F1") (pin "P$2") (pinfunction "P$2_P$2") (pintype "passive"))
      (node (ref "J4") (pin "2") (pinfunction "2_2") (pintype "passive"))
    )
    (net (code "64") (name "Net-(JP6-Pad2)") (class "Default")
      (node (ref "JP6") (pin "2") (pinfunction "2_2") (pintype "passive"))
      (node (ref "JP7") (pin "2") (pinfunction "2_2") (pintype "passive"))
    )
    (net (code "65") (name "Net-(JP10-Pad2)") (class "Default")
      (node (ref "JP10") (pin "2") (pinfunction "2_2") (pintype "passive"))
      (node (ref "JP4") (pin "2") (pinfunction "2_2") (pintype "passive"))
      (node (ref "JP8") (pin "2") (pinfunction "2_2") (pintype "passive"))
      (node (ref "JP9") (pin "2") (pinfunction "2_2") (pintype "passive"))
    )
    (net (code "66") (name "Net-(LED1-PadA)") (class "Default")
      (node (ref "LED1") (pin "A") (pinfunction "A_A") (pintype "passive"))
      (node (ref "R1") (pin "1") (pinfunction "1_1") (pintype "passive"))
    )
    (net (code "67") (name "Net-(P1-MOT-1A)") (class "Default")
      (node (ref "JP11") (pin "2") (pinfunction "2_2") (pintype "passive"))
      (node (ref "P1") (pin "1A") (pinfunction "MOT-1A_1A") (pintype "power_in"))
    )
    (net (code "68") (name "Net-(P1-MOT-1B)") (class "Default")
      (node (ref "JP11") (pin "1") (pinfunction "1_1") (pintype "passive"))
      (node (ref "P1") (pin "1B") (pinfunction "MOT-1B_1B") (pintype "power_in"))
    )
    (net (code "69") (name "Net-(P1-MOT-2A)") (class "Default")
      (node (ref "JP11") (pin "3") (pinfunction "3_3") (pintype "passive"))
      (node (ref "P1") (pin "2A") (pinfunction "MOT-2A_2A") (pintype "power_in"))
    )
    (net (code "70") (name "Net-(P1-MOT-2B)") (class "Default")
      (node (ref "JP11") (pin "4") (pinfunction "4_4") (pintype "passive"))
      (node (ref "P1") (pin "2B") (pinfunction "MOT-2B_2B") (pintype "power_in"))
    )
    (net (code "71") (name "Net-(P1-PadMS1)") (class "Default")
      (node (ref "P1") (pin "MS1") (pinfunction "MS1_MS1") (pintype "input"))
      (node (ref "SJ12") (pin "1") (pinfunction "1_1") (pintype "passive"))
    )
    (net (code "72") (name "Net-(P1-PadMS2)") (class "Default")
      (node (ref "P1") (pin "MS2") (pinfunction "MS2_MS2") (pintype "input"))
      (node (ref "SJ7") (pin "1") (pinfunction "1_1") (pintype "passive"))
    )
    (net (code "73") (name "Net-(P1-PadMS3)") (class "Default")
      (node (ref "P1") (pin "MS3") (pinfunction "MS3_MS3") (pintype "input"))
      (node (ref "SJ2") (pin "1") (pinfunction "1_1") (pintype "passive"))
    )
    (net (code "74") (name "Net-(P1-~{RESET})") (class "Default")
      (node (ref "P1") (pin "!RST") (pinfunction "~{RESET}_!RST") (pintype "input"))
      (node (ref "P1") (pin "!SLP") (pinfunction "~{SLEEP}_!SLP") (pintype "input"))
    )
    (net (code "75") (name "Net-(P2-MOT-1A)") (class "Default")
      (node (ref "JP12") (pin "2") (pinfunction "2_2") (pintype "passive"))
      (node (ref "P2") (pin "1A") (pinfunction "MOT-1A_1A") (pintype "power_in"))
    )
    (net (code "76") (name "Net-(P2-MOT-1B)") (class "Default")
      (node (ref "JP12") (pin "1") (pinfunction "1_1") (pintype "passive"))
      (node (ref "P2") (pin "1B") (pinfunction "MOT-1B_1B") (pintype "power_in"))
    )
    (net (code "77") (name "Net-(P2-MOT-2A)") (class "Default")
      (node (ref "JP12") (pin "3") (pinfunction "3_3") (pintype "passive"))
      (node (ref "P2") (pin "2A") (pinfunction "MOT-2A_2A") (pintype "power_in"))
    )
    (net (code "78") (name "Net-(P2-MOT-2B)") (class "Default")
      (node (ref "JP12") (pin "4") (pinfunction "4_4") (pintype "passive"))
      (node (ref "P2") (pin "2B") (pinfunction "MOT-2B_2B") (pintype "power_in"))
    )
    (net (code "79") (name "Net-(P2-PadMS1)") (class "Default")
      (node (ref "P2") (pin "MS1") (pinfunction "MS1_MS1") (pintype "input"))
      (node (ref "SJ13") (pin "1") (pinfunction "1_1") (pintype "passive"))
    )
    (net (code "80") (name "Net-(P2-PadMS2)") (class "Default")
      (node (ref "P2") (pin "MS2") (pinfunction "MS2_MS2") (pintype "input"))
      (node (ref "SJ8") (pin "1") (pinfunction "1_1") (pintype "passive"))
    )
    (net (code "81") (name "Net-(P2-PadMS3)") (class "Default")
      (node (ref "P2") (pin "MS3") (pinfunction "MS3_MS3") (pintype "input"))
      (node (ref "SJ3") (pin "1") (pinfunction "1_1") (pintype "passive"))
    )
    (net (code "82") (name "Net-(P2-~{RESET})") (class "Default")
      (node (ref "P2") (pin "!RST") (pinfunction "~{RESET}_!RST") (pintype "input"))
      (node (ref "P2") (pin "!SLP") (pinfunction "~{SLEEP}_!SLP") (pintype "input"))
    )
    (net (code "83") (name "Net-(P3-MOT-1A)") (class "Default")
      (node (ref "JP15") (pin "2") (pinfunction "2_2") (pintype "passive"))
      (node (ref "P3") (pin "1A") (pinfunction "MOT-1A_1A") (pintype "power_in"))
    )
    (net (code "84") (name "Net-(P3-MOT-1B)") (class "Default")
      (node (ref "JP15") (pin "1") (pinfunction "1_1") (pintype "passive"))
      (node (ref "P3") (pin "1B") (pinfunction "MOT-1B_1B") (pintype "power_in"))
    )
    (net (code "85") (name "Net-(P3-MOT-2A)") (class "Default")
      (node (ref "JP15") (pin "3") (pinfunction "3_3") (pintype "passive"))
      (node (ref "P3") (pin "2A") (pinfunction "MOT-2A_2A") (pintype "power_in"))
    )
    (net (code "86") (name "Net-(P3-MOT-2B)") (class "Default")
      (node (ref "JP15") (pin "4") (pinfunction "4_4") (pintype "passive"))
      (node (ref "P3") (pin "2B") (pinfunction "MOT-2B_2B") (pintype "power_in"))
    )
    (net (code "87") (name "Net-(P3-PadMS1)") (class "Default")
      (node (ref "P3") (pin "MS1") (pinfunction "MS1_MS1") (pintype "input"))
      (node (ref "SJ14") (pin "1") (pinfunction "1_1") (pintype "passive"))
    )
    (net (code "88") (name "Net-(P3-PadMS2)") (class "Default")
      (node (ref "P3") (pin "MS2") (pinfunction "MS2_MS2") (pintype "input"))
      (node (ref "SJ9") (pin "1") (pinfunction "1_1") (pintype "passive"))
    )
    (net (code "89") (name "Net-(P3-PadMS3)") (class "Default")
      (node (ref "P3") (pin "MS3") (pinfunction "MS3_MS3") (pintype "input"))
      (node (ref "SJ4") (pin "1") (pinfunction "1_1") (pintype "passive"))
    )
    (net (code "90") (name "Net-(P3-~{RESET})") (class "Default")
      (node (ref "P3") (pin "!RST") (pinfunction "~{RESET}_!RST") (pintype "input"))
      (node (ref "P3") (pin "!SLP") (pinfunction "~{SLEEP}_!SLP") (pintype "input"))
    )
    (net (code "91") (name "Net-(P4-MOT-1A)") (class "Default")
      (node (ref "JP13") (pin "2") (pinfunction "2_2") (pintype "passive"))
      (node (ref "P4") (pin "1A") (pinfunction "MOT-1A_1A") (pintype "power_in"))
    )
    (net (code "92") (name "Net-(P4-MOT-1B)") (class "Default")
      (node (ref "JP13") (pin "1") (pinfunction "1_1") (pintype "passive"))
      (node (ref "P4") (pin "1B") (pinfunction "MOT-1B_1B") (pintype "power_in"))
    )
    (net (code "93") (name "Net-(P4-MOT-2A)") (class "Default")
      (node (ref "JP13") (pin "3") (pinfunction "3_3") (pintype "passive"))
      (node (ref "P4") (pin "2A") (pinfunction "MOT-2A_2A") (pintype "power_in"))
    )
    (net (code "94") (name "Net-(P4-MOT-2B)") (class "Default")
      (node (ref "JP13") (pin "4") (pinfunction "4_4") (pintype "passive"))
      (node (ref "P4") (pin "2B") (pinfunction "MOT-2B_2B") (pintype "power_in"))
    )
    (net (code "95") (name "Net-(P4-PadMS1)") (class "Default")
      (node (ref "P4") (pin "MS1") (pinfunction "MS1_MS1") (pintype "input"))
      (node (ref "SJ15") (pin "1") (pinfunction "1_1") (pintype "passive"))
    )
    (net (code "96") (name "Net-(P4-PadMS2)") (class "Default")
      (node (ref "P4") (pin "MS2") (pinfunction "MS2_MS2") (pintype "input"))
      (node (ref "SJ10") (pin "1") (pinfunction "1_1") (pintype "passive"))
    )
    (net (code "97") (name "Net-(P4-PadMS3)") (class "Default")
      (node (ref "P4") (pin "MS3") (pinfunction "MS3_MS3") (pintype "input"))
      (node (ref "SJ5") (pin "1") (pinfunction "1_1") (pintype "passive"))
    )
    (net (code "98") (name "Net-(P4-~{RESET})") (class "Default")
      (node (ref "P4") (pin "!RST") (pinfunction "~{RESET}_!RST") (pintype "input"))
      (node (ref "P4") (pin "!SLP") (pinfunction "~{SLEEP}_!SLP") (pintype "input"))
    )
    (net (code "99") (name "Net-(P5-MOT-1A)") (class "Default")
      (node (ref "JP14") (pin "2") (pinfunction "2_2") (pintype "passive"))
      (node (ref "P5") (pin "1A") (pinfunction "MOT-1A_1A") (pintype "power_in"))
    )
    (net (code "100") (name "Net-(P5-MOT-1B)") (class "Default")
      (node (ref "JP14") (pin "1") (pinfunction "1_1") (pintype "passive"))
      (node (ref "P5") (pin "1B") (pinfunction "MOT-1B_1B") (pintype "power_in"))
    )
    (net (code "101") (name "Net-(P5-MOT-2A)") (class "Default")
      (node (ref "JP14") (pin "3") (pinfunction "3_3") (pintype "passive"))
      (node (ref "P5") (pin "2A") (pinfunction "MOT-2A_2A") (pintype "power_in"))
    )
    (net (code "102") (name "Net-(P5-MOT-2B)") (class "Default")
      (node (ref "JP14") (pin "4") (pinfunction "4_4") (pintype "passive"))
      (node (ref "P5") (pin "2B") (pinfunction "MOT-2B_2B") (pintype "power_in"))
    )
    (net (code "103") (name "Net-(P5-PadMS1)") (class "Default")
      (node (ref "P5") (pin "MS1") (pinfunction "MS1_MS1") (pintype "input"))
      (node (ref "SJ16") (pin "1") (pinfunction "1_1") (pintype "passive"))
    )
    (net (code "104") (name "Net-(P5-PadMS2)") (class "Default")
      (node (ref "P5") (pin "MS2") (pinfunction "MS2_MS2") (pintype "input"))
      (node (ref "SJ11") (pin "1") (pinfunction "1_1") (pintype "passive"))
    )
    (net (code "105") (name "Net-(P5-PadMS3)") (class "Default")
      (node (ref "P5") (pin "MS3") (pinfunction "MS3_MS3") (pintype "input"))
      (node (ref "SJ6") (pin "1") (pinfunction "1_1") (pintype "passive"))
    )
    (net (code "106") (name "Net-(P5-~{RESET})") (class "Default")
      (node (ref "P5") (pin "!RST") (pinfunction "~{RESET}_!RST") (pintype "input"))
      (node (ref "P5") (pin "!SLP") (pinfunction "~{SLEEP}_!SLP") (pintype "input"))
    )
    (net (code "107") (name "Net-(Q1-D)") (class "Default")
      (node (ref "D2") (pin "C") (pinfunction "C_C") (pintype "passive"))
      (node (ref "F1") (pin "P$1") (pinfunction "P$1_P$1") (pintype "passive"))
      (node (ref "Q1") (pin "3") (pinfunction "D_3") (pintype "passive"))
    )
    (net (code "108") (name "Net-(Q1-G)") (class "Default")
      (node (ref "Q1") (pin "1") (pinfunction "G_1") (pintype "passive"))
      (node (ref "R3") (pin "2") (pinfunction "2_2") (pintype "passive"))
    )
    (net (code "109") (name "Net-(Q2-D)") (class "Default")
      (node (ref "J7") (pin "1") (pinfunction "1_1") (pintype "power_in"))
      (node (ref "J7") (pin "2") (pinfunction "2_2") (pintype "power_in"))
      (node (ref "Q2") (pin "5-8") (pinfunction "D_5-8") (pintype "passive"))
    )
    (net (code "110") (name "Net-(Q2-G)") (class "Default")
      (node (ref "Q2") (pin "4") (pinfunction "G_4") (pintype "passive"))
      (node (ref "R9") (pin "2") (pinfunction "2_2") (pintype "passive"))
    )
    (net (code "111") (name "Net-(Q3-D)") (class "Default")
      (node (ref "J9") (pin "1") (pinfunction "1_1") (pintype "power_in"))
      (node (ref "J9") (pin "2") (pinfunction "2_2") (pintype "power_in"))
      (node (ref "Q3") (pin "5-8") (pinfunction "D_5-8") (pintype "passive"))
    )
    (net (code "112") (name "Net-(Q3-G)") (class "Default")
      (node (ref "Q3") (pin "4") (pinfunction "G_4") (pintype "passive"))
      (node (ref "R11") (pin "2") (pinfunction "2_2") (pintype "passive"))
    )
    (net (code "113") (name "Net-(Q4-D)") (class "Default")
      (node (ref "J10") (pin "1") (pinfunction "1_1") (pintype "power_in"))
      (node (ref "J10") (pin "2") (pinfunction "2_2") (pintype "power_in"))
      (node (ref "Q4") (pin "5-8") (pinfunction "D_5-8") (pintype "passive"))
    )
    (net (code "114") (name "Net-(Q4-G)") (class "Default")
      (node (ref "Q4") (pin "4") (pinfunction "G_4") (pintype "passive"))
      (node (ref "R15") (pin "2") (pinfunction "2_2") (pintype "passive"))
    )
    (net (code "115") (name "Net-(U1-CB)") (class "Default")
      (node (ref "C4") (pin "2") (pinfunction "2_2") (pintype "passive"))
      (node (ref "U1") (pin "1") (pinfunction "CB_1") (pintype "passive"))
    )
    (net (code "116") (name "Net-(U1-FB)") (class "Default")
      (node (ref "R4") (pin "2") (pinfunction "2_2") (pintype "passive"))
      (node (ref "R5") (pin "1") (pinfunction "1_1") (pintype "passive"))
      (node (ref "U1") (pin "3") (pinfunction "FB_3") (pintype "passive"))
    )
    (net (code "117") (name "Net-(U1-SW)") (class "Default")
      (node (ref "C4") (pin "1") (pinfunction "1_1") (pintype "passive"))
      (node (ref "D1") (pin "C") (pinfunction "C_C") (pintype "passive"))
      (node (ref "L1") (pin "1") (pinfunction "1_1") (pintype "passive"))
      (node (ref "U1") (pin "6") (pinfunction "SW_6") (pintype "passive"))
    )
    (net (code "118") (name "Net-(U5-D+)") (class "Default")
      (node (ref "R7") (pin "2") (pinfunction "2_2") (pintype "passive"))
      (node (ref "U5") (pin "5") (pinfunction "D+_5") (pintype "bidirectional"))
    )
    (net (code "119") (name "Net-(U5-D-)") (class "Default")
      (node (ref "R6") (pin "2") (pinfunction "2_2") (pintype "passive"))
      (node (ref "U5") (pin "4") (pinfunction "D-_4") (pintype "bidirectional"))
    )
    (net (code "120") (name "Net-(U5-UCAP)") (class "Default")
      (node (ref "C9") (pin "2") (pinfunction "2_2") (pintype "passive"))
      (node (ref "U5") (pin "7") (pinfunction "UCAP_7") (pintype "power_in"))
    )
    (net (code "121") (name "unconnected-(J2-DAT1-Pad8)") (class "Default")
      (node (ref "J2") (pin "8") (pinfunction "DAT1_8") (pintype "bidirectional"))
    )
    (net (code "122") (name "unconnected-(J2-DAT2-Pad1)") (class "Default")
      (node (ref "J2") (pin "1") (pinfunction "DAT2_1") (pintype "bidirectional"))
    )
    (net (code "123") (name "unconnected-(U2-IO3-Pad4)") (class "Default")
      (node (ref "U2") (pin "4") (pinfunction "IO3_4") (pintype "bidirectional"))
    )
    (net (code "124") (name "unconnected-(U2-IO4-Pad6)") (class "Default")
      (node (ref "U2") (pin "6") (pinfunction "IO4_6") (pintype "bidirectional"))
    )
  )
)
